# W504A.net
KiCad netlist of a schematic drawn in EAGLE
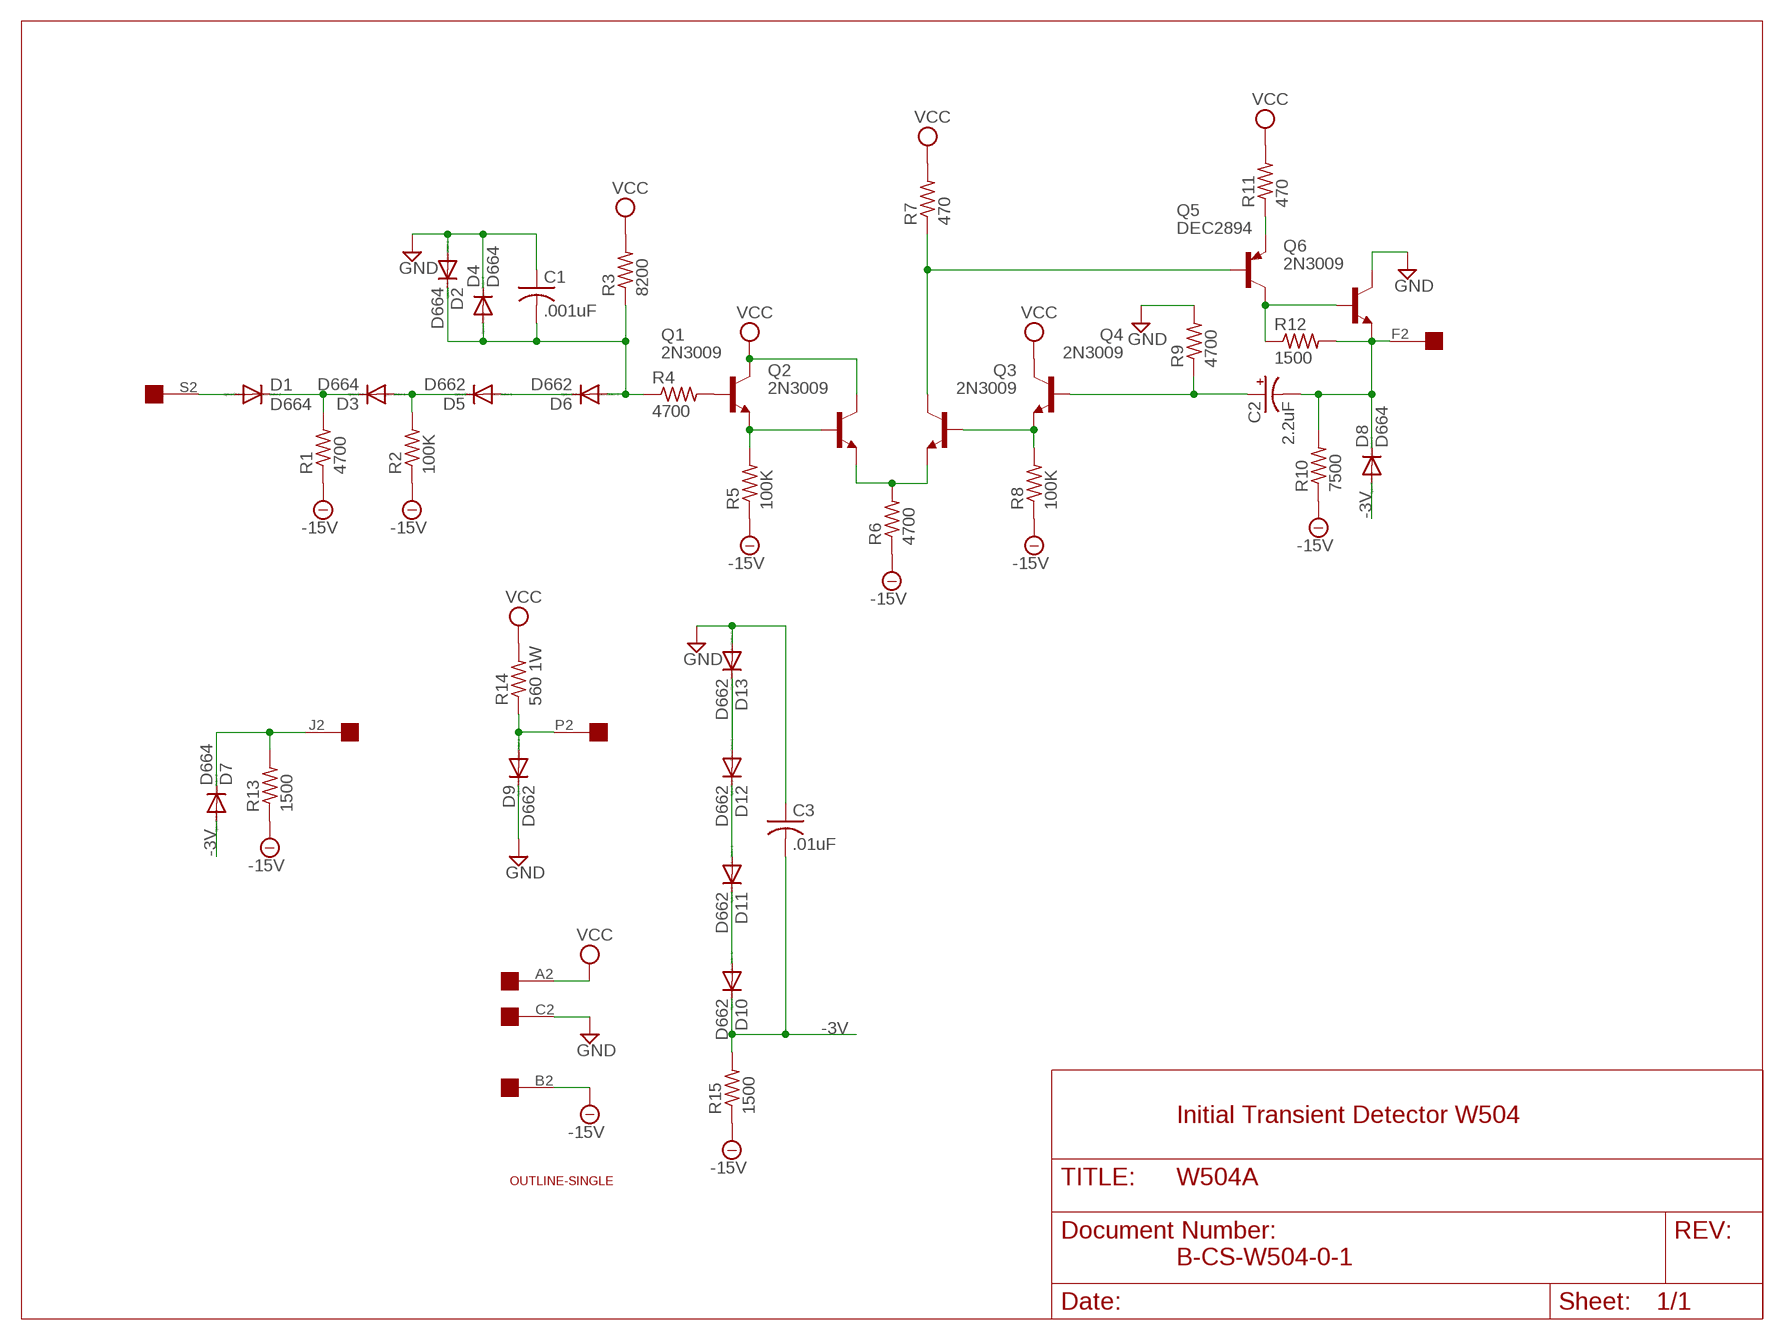
[diagram p0: schematic, sheet 1]

(export (version "E")
  (design (tool "Eeschema 10.0.6"))
  (components
    (comp (ref "C1")
      (value ".001uF")
      (footprint "eagle-import:C150-054X183")
      (libsource (lib "eagle-import") (part "C-US150-054X183"))
    )
    (comp (ref "C2")
      (value "2.2uF")
      (footprint "eagle-import:E12-4")
      (libsource (lib "eagle-import") (part "CPOL-USE12-4AXIAL"))
    )
    (comp (ref "C3")
      (value ".01uF")
      (footprint "eagle-import:C150-054X183")
      (libsource (lib "eagle-import") (part "C-US150-054X183"))
    )
    (comp (ref "D1")
      (value "D664")
      (footprint "eagle-import:DO35-10")
      (libsource (lib "eagle-import") (part "DIODE-DO35-10"))
    )
    (comp (ref "D2")
      (value "D664")
      (footprint "eagle-import:DO35-10")
      (libsource (lib "eagle-import") (part "DIODE-DO35-10"))
    )
    (comp (ref "D3")
      (value "D664")
      (footprint "eagle-import:DO35-10")
      (libsource (lib "eagle-import") (part "DIODE-DO35-10"))
    )
    (comp (ref "D4")
      (value "D664")
      (footprint "eagle-import:DO35-10")
      (libsource (lib "eagle-import") (part "DIODE-DO35-10"))
    )
    (comp (ref "D5")
      (value "D662")
      (footprint "eagle-import:DO35-10")
      (libsource (lib "eagle-import") (part "DIODE-DO35-10"))
    )
    (comp (ref "D6")
      (value "D662")
      (footprint "eagle-import:DO35-10")
      (libsource (lib "eagle-import") (part "DIODE-DO35-10"))
    )
    (comp (ref "D7")
      (value "D664")
      (footprint "eagle-import:DO35-10")
      (libsource (lib "eagle-import") (part "DIODE-DO35-10"))
    )
    (comp (ref "D8")
      (value "D664")
      (footprint "eagle-import:DO35-10")
      (libsource (lib "eagle-import") (part "DIODE-DO35-10"))
    )
    (comp (ref "D9")
      (value "D662")
      (footprint "eagle-import:DO35-10")
      (libsource (lib "eagle-import") (part "DIODE-DO35-10"))
    )
    (comp (ref "D10")
      (value "D662")
      (footprint "eagle-import:DO35-10")
      (libsource (lib "eagle-import") (part "DIODE-DO35-10"))
    )
    (comp (ref "D11")
      (value "D662")
      (footprint "eagle-import:DO35-10")
      (libsource (lib "eagle-import") (part "DIODE-DO35-10"))
    )
    (comp (ref "D12")
      (value "D662")
      (footprint "eagle-import:DO35-10")
      (libsource (lib "eagle-import") (part "DIODE-DO35-10"))
    )
    (comp (ref "D13")
      (value "D662")
      (footprint "eagle-import:DO35-10")
      (libsource (lib "eagle-import") (part "DIODE-DO35-10"))
    )
    (comp (ref "Q1")
      (value "2N3009")
      (footprint "eagle-import:TO5")
      (libsource (lib "eagle-import") (part "-NPN-TO5"))
    )
    (comp (ref "Q2")
      (value "2N3009")
      (footprint "eagle-import:TO5")
      (libsource (lib "eagle-import") (part "-NPN-TO5"))
    )
    (comp (ref "Q3")
      (value "2N3009")
      (footprint "eagle-import:TO5")
      (libsource (lib "eagle-import") (part "-NPN-TO5"))
    )
    (comp (ref "Q4")
      (value "2N3009")
      (footprint "eagle-import:TO5")
      (libsource (lib "eagle-import") (part "-NPN-TO5"))
    )
    (comp (ref "Q5")
      (value "DEC2894")
      (footprint "eagle-import:TO5")
      (libsource (lib "eagle-import") (part "-PNP-TO5"))
    )
    (comp (ref "Q6")
      (value "2N3009")
      (footprint "eagle-import:TO5")
      (libsource (lib "eagle-import") (part "-NPN-TO5"))
    )
    (comp (ref "R1")
      (value "4700")
      (footprint "eagle-import:0207_10")
      (libsource (lib "eagle-import") (part "R-US_0207/10"))
    )
    (comp (ref "R2")
      (value "100K")
      (footprint "eagle-import:0207_10")
      (libsource (lib "eagle-import") (part "R-US_0207/10"))
    )
    (comp (ref "R3")
      (value "8200")
      (footprint "eagle-import:0207_10")
      (libsource (lib "eagle-import") (part "R-US_0207/10"))
    )
    (comp (ref "R4")
      (value "4700")
      (footprint "eagle-import:0207_10")
      (libsource (lib "eagle-import") (part "R-US_0207/10"))
    )
    (comp (ref "R5")
      (value "100K")
      (footprint "eagle-import:0207_10")
      (libsource (lib "eagle-import") (part "R-US_0207/10"))
    )
    (comp (ref "R6")
      (value "4700")
      (footprint "eagle-import:0207_10")
      (libsource (lib "eagle-import") (part "R-US_0207/10"))
    )
    (comp (ref "R7")
      (value "470")
      (footprint "eagle-import:0207_10")
      (libsource (lib "eagle-import") (part "R-US_0207/10"))
    )
    (comp (ref "R8")
      (value "100K")
      (footprint "eagle-import:0207_10")
      (libsource (lib "eagle-import") (part "R-US_0207/10"))
    )
    (comp (ref "R9")
      (value "4700")
      (footprint "eagle-import:0207_10")
      (libsource (lib "eagle-import") (part "R-US_0207/10"))
    )
    (comp (ref "R10")
      (value "7500")
      (footprint "eagle-import:0207_10")
      (libsource (lib "eagle-import") (part "R-US_0207/10"))
    )
    (comp (ref "R11")
      (value "470")
      (footprint "eagle-import:0207_10")
      (libsource (lib "eagle-import") (part "R-US_0207/10"))
    )
    (comp (ref "R12")
      (value "1500")
      (footprint "eagle-import:0207_10")
      (libsource (lib "eagle-import") (part "R-US_0207/10"))
    )
    (comp (ref "R13")
      (value "1500")
      (footprint "eagle-import:0207_10")
      (libsource (lib "eagle-import") (part "R-US_0207/10"))
    )
    (comp (ref "R14")
      (value "560 1W")
      (footprint "eagle-import:0617_22")
      (libsource (lib "eagle-import") (part "R-US_0617/22"))
    )
    (comp (ref "R15")
      (value "1500")
      (footprint "eagle-import:0207_10")
      (libsource (lib "eagle-import") (part "R-US_0207/10"))
    )
    (comp (ref "U$1")
      (value "OUTLINE-SINGLE")
      (footprint "eagle-import:SINGLE")
      (libsource (lib "eagle-import") (part "OUTLINE-SINGLE"))
    )
    (comp (ref "U$2")
      (value "EDGE-1")
      (footprint "eagle-import:EDGE-CON1")
      (libsource (lib "eagle-import") (part "EDGE-1"))
    )
  )
  (nets
    (net (code "1") (name "-15V") (class "Default")
      (node (ref "R1") (pin "1") (pinfunction "1_1") (pintype "passive"))
      (node (ref "R10") (pin "1") (pinfunction "1_1") (pintype "passive"))
      (node (ref "R13") (pin "1") (pinfunction "1_1") (pintype "passive"))
      (node (ref "R15") (pin "1") (pinfunction "1_1") (pintype "passive"))
      (node (ref "R2") (pin "1") (pinfunction "1_1") (pintype "passive"))
      (node (ref "R5") (pin "1") (pinfunction "1_1") (pintype "passive"))
      (node (ref "R6") (pin "1") (pinfunction "1_1") (pintype "passive"))
      (node (ref "R8") (pin "1") (pinfunction "1_1") (pintype "passive"))
      (node (ref "U$2") (pin "B2") (pinfunction "1_B2") (pintype "bidirectional"))
    )
    (net (code "2") (name "/-3V") (class "Default")
      (node (ref "C3") (pin "2") (pinfunction "2_2") (pintype "passive"))
      (node (ref "D10") (pin "C") (pinfunction "C_C") (pintype "passive"))
      (node (ref "D7") (pin "A") (pinfunction "A_A") (pintype "passive"))
      (node (ref "D8") (pin "A") (pinfunction "A_A") (pintype "passive"))
      (node (ref "R15") (pin "2") (pinfunction "2_2") (pintype "passive"))
    )
    (net (code "3") (name "GND") (class "Default")
      (node (ref "C1") (pin "1") (pinfunction "1_1") (pintype "passive"))
      (node (ref "C3") (pin "1") (pinfunction "1_1") (pintype "passive"))
      (node (ref "D13") (pin "A") (pinfunction "A_A") (pintype "passive"))
      (node (ref "D2") (pin "A") (pinfunction "A_A") (pintype "passive"))
      (node (ref "D4") (pin "C") (pinfunction "C_C") (pintype "passive"))
      (node (ref "D9") (pin "C") (pinfunction "C_C") (pintype "passive"))
      (node (ref "Q6") (pin "3") (pinfunction "C_3") (pintype "passive"))
      (node (ref "R9") (pin "2") (pinfunction "2_2") (pintype "passive"))
      (node (ref "U$2") (pin "C2") (pinfunction "1_C2") (pintype "bidirectional"))
    )
    (net (code "4") (name "Net-(C1-Pad2)") (class "Default")
      (node (ref "C1") (pin "2") (pinfunction "2_2") (pintype "passive"))
      (node (ref "D2") (pin "C") (pinfunction "C_C") (pintype "passive"))
      (node (ref "D4") (pin "A") (pinfunction "A_A") (pintype "passive"))
      (node (ref "D6") (pin "A") (pinfunction "A_A") (pintype "passive"))
      (node (ref "R3") (pin "1") (pinfunction "1_1") (pintype "passive"))
      (node (ref "R4") (pin "1") (pinfunction "1_1") (pintype "passive"))
    )
    (net (code "5") (name "Net-(D1-PadC)") (class "Default")
      (node (ref "D1") (pin "C") (pinfunction "C_C") (pintype "passive"))
      (node (ref "D3") (pin "C") (pinfunction "C_C") (pintype "passive"))
      (node (ref "R1") (pin "2") (pinfunction "2_2") (pintype "passive"))
    )
    (net (code "6") (name "Net-(D3-PadA)") (class "Default")
      (node (ref "D3") (pin "A") (pinfunction "A_A") (pintype "passive"))
      (node (ref "D5") (pin "C") (pinfunction "C_C") (pintype "passive"))
      (node (ref "R2") (pin "2") (pinfunction "2_2") (pintype "passive"))
    )
    (net (code "7") (name "Net-(D5-PadA)") (class "Default")
      (node (ref "D5") (pin "A") (pinfunction "A_A") (pintype "passive"))
      (node (ref "D6") (pin "C") (pinfunction "C_C") (pintype "passive"))
    )
    (net (code "8") (name "Net-(D10-PadA)") (class "Default")
      (node (ref "D10") (pin "A") (pinfunction "A_A") (pintype "passive"))
      (node (ref "D11") (pin "C") (pinfunction "C_C") (pintype "passive"))
    )
    (net (code "9") (name "Net-(D11-PadA)") (class "Default")
      (node (ref "D11") (pin "A") (pinfunction "A_A") (pintype "passive"))
      (node (ref "D12") (pin "C") (pinfunction "C_C") (pintype "passive"))
    )
    (net (code "10") (name "Net-(D12-PadA)") (class "Default")
      (node (ref "D12") (pin "A") (pinfunction "A_A") (pintype "passive"))
      (node (ref "D13") (pin "C") (pinfunction "C_C") (pintype "passive"))
    )
    (net (code "11") (name "Net-(Q1-B)") (class "Default")
      (node (ref "Q1") (pin "2") (pinfunction "B_2") (pintype "passive"))
      (node (ref "R4") (pin "2") (pinfunction "2_2") (pintype "passive"))
    )
    (net (code "12") (name "Net-(Q1-E)") (class "Default")
      (node (ref "Q1") (pin "1") (pinfunction "E_1") (pintype "passive"))
      (node (ref "Q2") (pin "2") (pinfunction "B_2") (pintype "passive"))
      (node (ref "R5") (pin "2") (pinfunction "2_2") (pintype "passive"))
    )
    (net (code "13") (name "Net-(Q2-E)") (class "Default")
      (node (ref "Q2") (pin "1") (pinfunction "E_1") (pintype "passive"))
      (node (ref "Q3") (pin "1") (pinfunction "E_1") (pintype "passive"))
      (node (ref "R6") (pin "2") (pinfunction "2_2") (pintype "passive"))
    )
    (net (code "14") (name "Net-(Q3-B)") (class "Default")
      (node (ref "Q3") (pin "2") (pinfunction "B_2") (pintype "passive"))
      (node (ref "Q4") (pin "1") (pinfunction "E_1") (pintype "passive"))
      (node (ref "R8") (pin "2") (pinfunction "2_2") (pintype "passive"))
    )
    (net (code "15") (name "Net-(Q3-C)") (class "Default")
      (node (ref "Q3") (pin "3") (pinfunction "C_3") (pintype "passive"))
      (node (ref "Q5") (pin "2") (pinfunction "B_2") (pintype "passive"))
      (node (ref "R7") (pin "1") (pinfunction "1_1") (pintype "passive"))
    )
    (net (code "16") (name "Net-(Q4-B)") (class "Default")
      (node (ref "C2") (pin "+") (pinfunction "+_+") (pintype "passive"))
      (node (ref "Q4") (pin "2") (pinfunction "B_2") (pintype "passive"))
      (node (ref "R9") (pin "1") (pinfunction "1_1") (pintype "passive"))
    )
    (net (code "17") (name "Net-(Q5-C)") (class "Default")
      (node (ref "Q5") (pin "3") (pinfunction "C_3") (pintype "passive"))
      (node (ref "Q6") (pin "2") (pinfunction "B_2") (pintype "passive"))
      (node (ref "R12") (pin "1") (pinfunction "1_1") (pintype "passive"))
    )
    (net (code "18") (name "Net-(Q5-E)") (class "Default")
      (node (ref "Q5") (pin "1") (pinfunction "E_1") (pintype "passive"))
      (node (ref "R11") (pin "1") (pinfunction "1_1") (pintype "passive"))
    )
    (net (code "19") (name "Net-(Q6-E)") (class "Default")
      (node (ref "C2") (pin "-") (pinfunction "-_-") (pintype "passive"))
      (node (ref "D8") (pin "C") (pinfunction "C_C") (pintype "passive"))
      (node (ref "Q6") (pin "1") (pinfunction "E_1") (pintype "passive"))
      (node (ref "R10") (pin "2") (pinfunction "2_2") (pintype "passive"))
      (node (ref "R12") (pin "2") (pinfunction "2_2") (pintype "passive"))
      (node (ref "U$2") (pin "F2") (pinfunction "1_F2") (pintype "bidirectional"))
    )
    (net (code "20") (name "Net-(U$2H-1)") (class "Default")
      (node (ref "D7") (pin "C") (pinfunction "C_C") (pintype "passive"))
      (node (ref "R13") (pin "2") (pinfunction "2_2") (pintype "passive"))
      (node (ref "U$2") (pin "J2") (pinfunction "1_J2") (pintype "bidirectional"))
    )
    (net (code "21") (name "Net-(U$2M-1)") (class "Default")
      (node (ref "D9") (pin "A") (pinfunction "A_A") (pintype "passive"))
      (node (ref "R14") (pin "1") (pinfunction "1_1") (pintype "passive"))
      (node (ref "U$2") (pin "P2") (pinfunction "1_P2") (pintype "bidirectional"))
    )
    (net (code "22") (name "Net-(U$2O-1)") (class "Default")
      (node (ref "D1") (pin "A") (pinfunction "A_A") (pintype "passive"))
      (node (ref "U$2") (pin "S2") (pinfunction "1_S2") (pintype "bidirectional"))
    )
    (net (code "23") (name "VCC") (class "Default")
      (node (ref "Q1") (pin "3") (pinfunction "C_3") (pintype "passive"))
      (node (ref "Q2") (pin "3") (pinfunction "C_3") (pintype "passive"))
      (node (ref "Q4") (pin "3") (pinfunction "C_3") (pintype "passive"))
      (node (ref "R11") (pin "2") (pinfunction "2_2") (pintype "passive"))
      (node (ref "R14") (pin "2") (pinfunction "2_2") (pintype "passive"))
      (node (ref "R3") (pin "2") (pinfunction "2_2") (pintype "passive"))
      (node (ref "R7") (pin "2") (pinfunction "2_2") (pintype "passive"))
      (node (ref "U$2") (pin "A2") (pinfunction "1_A2") (pintype "bidirectional"))
    )
  )
)
